# Sheet1.net
KiCad netlist of a schematic drawn in Altium Designer
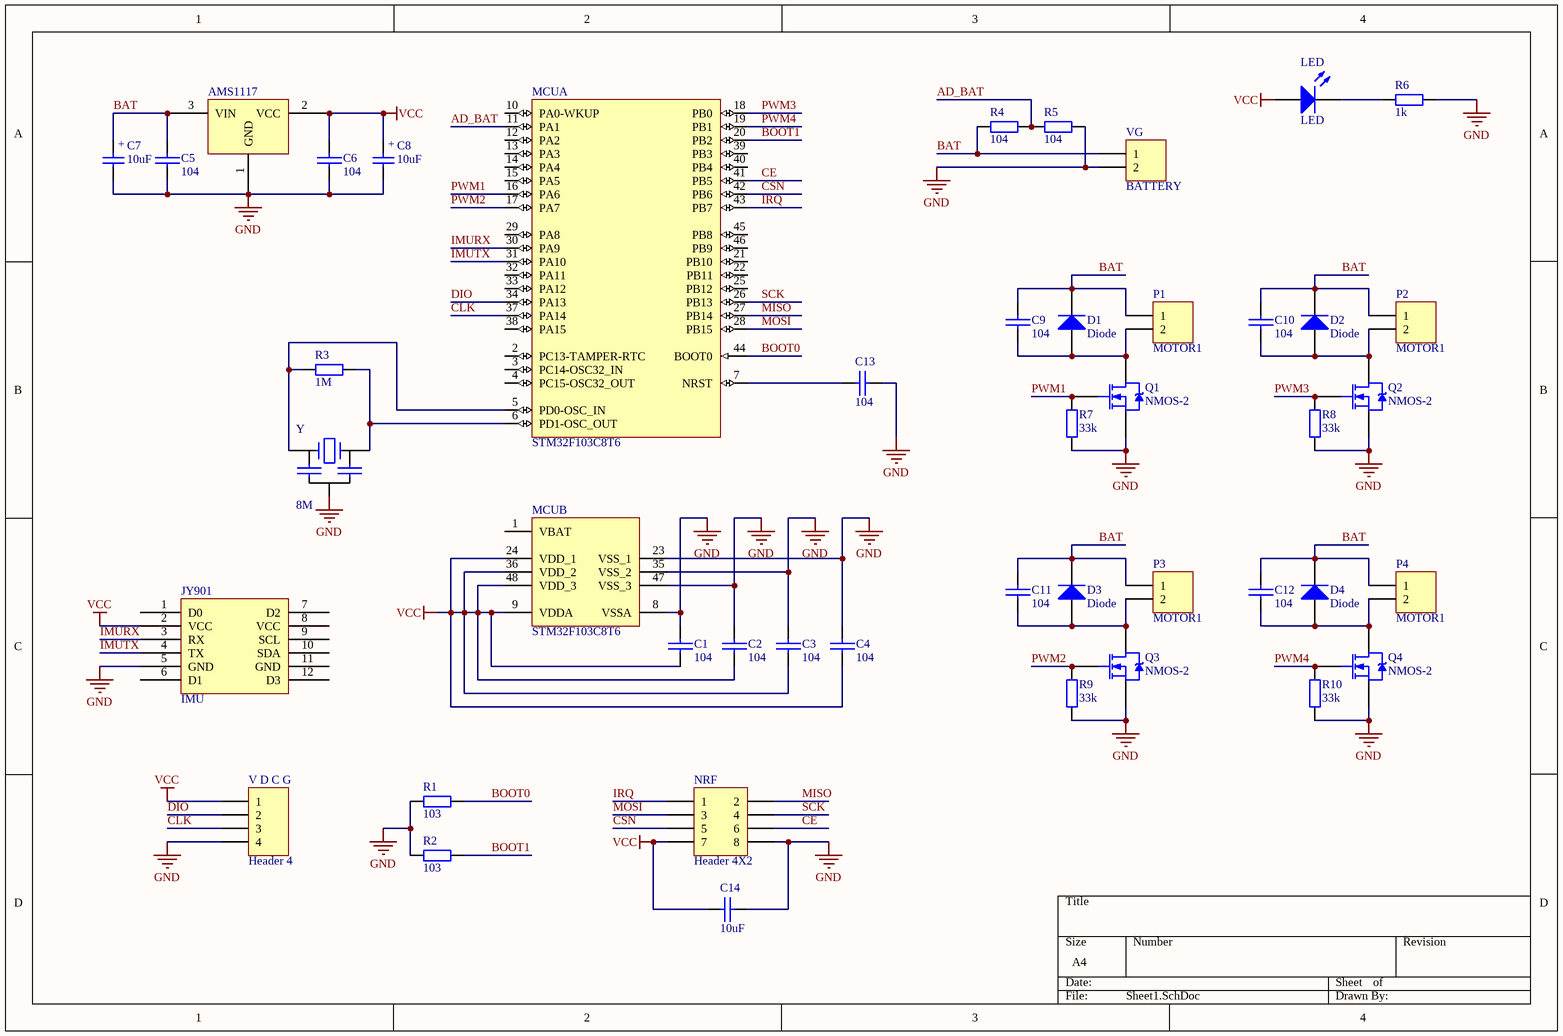
[diagram p0: Sheet1.SchDoc]

(export (version "E")
  (design (tool "Eeschema 10.0.6"))
  (components
    (comp (ref "AMS1117")
      (value "~")
      (footprint "LC-SOT-223")
      (libsource (lib "LC-Standard-FootPrints-AD-V1.00") (part "LC-SOT-233"))
    )
    (comp (ref "C1")
      (value "104")
      (footprint "C1608[0603]N")
      (description "贴片无极性电容")
      (fields (field (name "Comment") "CAP"))
      (libsource (lib "SkyWorks2") (part "CAP"))
    )
    (comp (ref "C2")
      (value "104")
      (footprint "C1608[0603]N")
      (description "贴片无极性电容")
      (fields (field (name "Comment") "CAP"))
      (libsource (lib "SkyWorks2") (part "CAP"))
    )
    (comp (ref "C3")
      (value "104")
      (footprint "C1608[0603]N")
      (description "贴片无极性电容")
      (fields (field (name "Comment") "CAP"))
      (libsource (lib "SkyWorks2") (part "CAP"))
    )
    (comp (ref "C4")
      (value "104")
      (footprint "C1608[0603]N")
      (description "贴片无极性电容")
      (fields (field (name "Comment") "CAP"))
      (libsource (lib "SkyWorks2") (part "CAP"))
    )
    (comp (ref "C5")
      (value "104")
      (footprint "C1608[0603]N")
      (description "贴片无极性电容")
      (fields (field (name "Comment") "cap smd"))
      (libsource (lib "SkyWorks2") (part "CAP"))
    )
    (comp (ref "C6")
      (value "104")
      (footprint "C1608[0603]N")
      (description "贴片无极性电容")
      (fields (field (name "Comment") "cap smd"))
      (libsource (lib "SkyWorks2") (part "CAP"))
    )
    (comp (ref "C7")
      (value "10uF")
      (footprint "C1206")
      (description "贴片极性电容")
      (fields (field (name "Comment") "Cap"))
      (libsource (lib "SkyWorks2") (part "Cap Pol S"))
    )
    (comp (ref "C8")
      (value "10uF")
      (footprint "C1206")
      (description "贴片极性电容")
      (fields (field (name "Comment") "Cap"))
      (libsource (lib "SkyWorks2") (part "Cap Pol S"))
    )
    (comp (ref "C9")
      (value "104")
      (footprint "C1608[0603]N")
      (description "贴片无极性电容")
      (fields (field (name "Comment") "cap smd"))
      (libsource (lib "SkyWorks2") (part "CAP"))
    )
    (comp (ref "C10")
      (value "104")
      (footprint "C1608[0603]N")
      (description "贴片无极性电容")
      (fields (field (name "Comment") "cap smd"))
      (libsource (lib "SkyWorks2") (part "CAP"))
    )
    (comp (ref "C11")
      (value "104")
      (footprint "C1608[0603]N")
      (description "贴片无极性电容")
      (fields (field (name "Comment") "cap smd"))
      (libsource (lib "SkyWorks2") (part "CAP"))
    )
    (comp (ref "C12")
      (value "104")
      (footprint "C1608[0603]N")
      (description "贴片无极性电容")
      (fields (field (name "Comment") "cap smd"))
      (libsource (lib "SkyWorks2") (part "CAP"))
    )
    (comp (ref "C13")
      (value "104")
      (footprint "C1608[0603]N")
      (description "贴片无极性电容")
      (fields (field (name "Comment") "cap smd"))
      (libsource (lib "SkyWorks2") (part "CAP"))
    )
    (comp (ref "C14")
      (value "10uF")
      (footprint "C2012[0805]N")
      (description "贴片无极性电容")
      (fields (field (name "Comment") "cap smd"))
      (libsource (lib "SkyWorks2") (part "CAP"))
    )
    (comp (ref "D1")
      (value "Diode")
      (footprint "D3216[1206]")
      (description "Default Diode")
      (fields (field (name "PUBLISHER") "Altium Limited"))
      (libsource (lib "SkyWorks2") (part "Diode"))
    )
    (comp (ref "D2")
      (value "Diode")
      (footprint "D3216[1206]")
      (description "Default Diode")
      (fields (field (name "PUBLISHER") "Altium Limited"))
      (libsource (lib "SkyWorks2") (part "Diode"))
    )
    (comp (ref "D3")
      (value "Diode")
      (footprint "D3216[1206]")
      (description "Default Diode")
      (fields (field (name "PUBLISHER") "Altium Limited"))
      (libsource (lib "SkyWorks2") (part "Diode"))
    )
    (comp (ref "D4")
      (value "Diode")
      (footprint "D3216[1206]")
      (description "Default Diode")
      (fields (field (name "PUBLISHER") "Altium Limited"))
      (libsource (lib "SkyWorks2") (part "Diode"))
    )
    (comp (ref "JY901") (value "IMU") (footprint "JY-901") (libsource (lib "JYMoudule") (part "JY901")))
    (comp (ref "LED")
      (value "LED")
      (footprint "3.2X1.6X1.1")
      (description "Typical RED, GREEN, YELLOW, AMBER GaAs LED")
      (fields (field (name "PUBLISHER") "Altium Limited"))
      (libsource (lib "SkyWorks2") (part "LED2"))
    )
    (comp (ref "MCU")
      (value "STM32F103C8T6")
      (footprint "STM-LQFP48_N")
      (libsource (lib "STMicroelectronics STM32 F1") (part "STM32F103C8T6"))
    )
    (comp (ref "NRF")
      (value "Header 4X2")
      (footprint "HDR2X4")
      (description "Header, 4-Pin, Dual row")
      (fields (field (name "PUBLISHER") "Altium Limited"))
      (libsource (lib "Miscellaneous Connectors") (part "Header 4X2"))
    )
    (comp (ref "P1")
      (value "MOTOR1")
      (footprint "HDR1X2")
      (description "Header, 2-Pin")
      (fields (field (name "PUBLISHER") "Altium Limited"))
      (libsource (lib "Miscellaneous Connectors") (part "Header 2"))
    )
    (comp (ref "P2")
      (value "MOTOR1")
      (footprint "HDR1X2")
      (description "Header, 2-Pin")
      (fields (field (name "PUBLISHER") "Altium Limited"))
      (libsource (lib "Miscellaneous Connectors") (part "Header 2"))
    )
    (comp (ref "P3")
      (value "MOTOR1")
      (footprint "HDR1X2")
      (description "Header, 2-Pin")
      (fields (field (name "PUBLISHER") "Altium Limited"))
      (libsource (lib "Miscellaneous Connectors") (part "Header 2"))
    )
    (comp (ref "P4")
      (value "MOTOR1")
      (footprint "HDR1X2")
      (description "Header, 2-Pin")
      (fields (field (name "PUBLISHER") "Altium Limited"))
      (libsource (lib "Miscellaneous Connectors") (part "Header 2"))
    )
    (comp (ref "Q1")
      (value "NMOS-2")
      (footprint "LC-SOT-23")
      (description "N-Channel Power MOSFET")
      (fields (field (name "PUBLISHER") "Altium Limited"))
      (libsource (lib "Miscellaneous Devices") (part "NMOS-2"))
    )
    (comp (ref "Q2")
      (value "NMOS-2")
      (footprint "LC-SOT-23")
      (description "N-Channel Power MOSFET")
      (fields (field (name "PUBLISHER") "Altium Limited"))
      (libsource (lib "Miscellaneous Devices") (part "NMOS-2"))
    )
    (comp (ref "Q3")
      (value "NMOS-2")
      (footprint "LC-SOT-23")
      (description "N-Channel Power MOSFET")
      (fields (field (name "PUBLISHER") "Altium Limited"))
      (libsource (lib "Miscellaneous Devices") (part "NMOS-2"))
    )
    (comp (ref "Q4")
      (value "NMOS-2")
      (footprint "LC-SOT-23")
      (description "N-Channel Power MOSFET")
      (fields (field (name "PUBLISHER") "Altium Limited"))
      (libsource (lib "Miscellaneous Devices") (part "NMOS-2"))
    )
    (comp (ref "R1")
      (value "103")
      (footprint "R1608[0603]")
      (fields (field (name "Comment") "RES1"))
      (libsource (lib "SkyWorks2") (part "RES1"))
    )
    (comp (ref "R2")
      (value "103")
      (footprint "R1608[0603]")
      (fields (field (name "Comment") "RES1"))
      (libsource (lib "SkyWorks2") (part "RES1"))
    )
    (comp (ref "R3")
      (value "1M")
      (footprint "R1608[0603]")
      (fields (field (name "Comment") "RES1"))
      (libsource (lib "SkyWorks2") (part "RES1"))
    )
    (comp (ref "R4")
      (value "104")
      (footprint "R1608[0603]")
      (fields (field (name "Comment") "RES1"))
      (libsource (lib "SkyWorks2") (part "RES1"))
    )
    (comp (ref "R5")
      (value "104")
      (footprint "R1608[0603]")
      (fields (field (name "Comment") "RES1"))
      (libsource (lib "SkyWorks2") (part "RES1"))
    )
    (comp (ref "R6")
      (value "1k")
      (footprint "R1608[0603]")
      (fields (field (name "Comment") "RES1"))
      (libsource (lib "SkyWorks2") (part "RES1"))
    )
    (comp (ref "R7")
      (value "33k")
      (footprint "R1608[0603]")
      (fields (field (name "Comment") "RES1"))
      (libsource (lib "SkyWorks2") (part "RES1"))
    )
    (comp (ref "R8")
      (value "33k")
      (footprint "R1608[0603]")
      (fields (field (name "Comment") "RES1"))
      (libsource (lib "SkyWorks2") (part "RES1"))
    )
    (comp (ref "R9")
      (value "33k")
      (footprint "R1608[0603]")
      (fields (field (name "Comment") "RES1"))
      (libsource (lib "SkyWorks2") (part "RES1"))
    )
    (comp (ref "R10")
      (value "33k")
      (footprint "R1608[0603]")
      (fields (field (name "Comment") "RES1"))
      (libsource (lib "SkyWorks2") (part "RES1"))
    )
    (comp (ref "V D C G")
      (value "Header 4")
      (footprint "HDR1X4")
      (description "Header, 4-Pin")
      (fields (field (name "PUBLISHER") "Altium Limited"))
      (libsource (lib "SkyWorks2") (part "Header 4"))
    )
    (comp (ref "VG")
      (value "BATTERY")
      (footprint "HDR1X2")
      (description "Header, 2-Pin")
      (fields (field (name "PUBLISHER") "Altium Limited"))
      (libsource (lib "Miscellaneous Connectors") (part "Header 2"))
    )
    (comp (ref "Y")
      (value "8M")
      (footprint "Crystal_C")
      (description "Crystal")
      (libsource (lib "SkyWorks2") (part "CRYSTAL_C"))
    )
  )
  (nets
    (net (code "1") (name "/AD_BAT") (class "Default")
      (node (ref "MCU") (pin "11") (pinfunction "PA1_11") (pintype "bidirectional"))
      (node (ref "R4") (pin "2") (pinfunction "2_2") (pintype "passive"))
      (node (ref "R5") (pin "1") (pinfunction "1_1") (pintype "passive"))
    )
    (net (code "2") (name "/BAT") (class "Default")
      (node (ref "AMS1117") (pin "3") (pinfunction "VIN_3") (pintype "passive"))
      (node (ref "C10") (pin "1") (pinfunction "1_1") (pintype "passive"))
      (node (ref "C11") (pin "1") (pinfunction "1_1") (pintype "passive"))
      (node (ref "C12") (pin "1") (pinfunction "1_1") (pintype "passive"))
      (node (ref "C5") (pin "1") (pinfunction "1_1") (pintype "passive"))
      (node (ref "C7") (pin "1") (pinfunction "+_1") (pintype "passive"))
      (node (ref "C9") (pin "1") (pinfunction "1_1") (pintype "passive"))
      (node (ref "D1") (pin "2") (pinfunction "K_2") (pintype "passive"))
      (node (ref "D2") (pin "2") (pinfunction "K_2") (pintype "passive"))
      (node (ref "D3") (pin "2") (pinfunction "K_2") (pintype "passive"))
      (node (ref "D4") (pin "2") (pinfunction "K_2") (pintype "passive"))
      (node (ref "P1") (pin "1") (pinfunction "1_1") (pintype "passive"))
      (node (ref "P2") (pin "1") (pinfunction "1_1") (pintype "passive"))
      (node (ref "P3") (pin "1") (pinfunction "1_1") (pintype "passive"))
      (node (ref "P4") (pin "1") (pinfunction "1_1") (pintype "passive"))
      (node (ref "R4") (pin "1") (pinfunction "1_1") (pintype "passive"))
      (node (ref "VG") (pin "1") (pinfunction "1_1") (pintype "passive"))
    )
    (net (code "3") (name "/BOOT0") (class "Default")
      (node (ref "MCU") (pin "44") (pinfunction "BOOT0_44") (pintype "input"))
      (node (ref "R1") (pin "2") (pinfunction "2_2") (pintype "passive"))
    )
    (net (code "4") (name "/BOOT1") (class "Default")
      (node (ref "MCU") (pin "20") (pinfunction "PB2_20") (pintype "bidirectional"))
      (node (ref "R2") (pin "2") (pinfunction "2_2") (pintype "passive"))
    )
    (net (code "5") (name "/CE") (class "Default")
      (node (ref "MCU") (pin "41") (pinfunction "PB5_41") (pintype "bidirectional"))
      (node (ref "NRF") (pin "6") (pinfunction "6_6") (pintype "passive"))
    )
    (net (code "6") (name "/CLK") (class "Default")
      (node (ref "MCU") (pin "37") (pinfunction "PA14_37") (pintype "bidirectional"))
      (node (ref "V D C G") (pin "3") (pinfunction "3_3") (pintype "passive"))
    )
    (net (code "7") (name "/CSN") (class "Default")
      (node (ref "MCU") (pin "42") (pinfunction "PB6_42") (pintype "bidirectional"))
      (node (ref "NRF") (pin "5") (pinfunction "5_5") (pintype "passive"))
    )
    (net (code "8") (name "/DIO") (class "Default")
      (node (ref "MCU") (pin "34") (pinfunction "PA13_34") (pintype "bidirectional"))
      (node (ref "V D C G") (pin "2") (pinfunction "2_2") (pintype "passive"))
    )
    (net (code "9") (name "/IMURX") (class "Default")
      (node (ref "JY901") (pin "3") (pinfunction "RX_3") (pintype "passive"))
      (node (ref "MCU") (pin "30") (pinfunction "PA9_30") (pintype "bidirectional"))
    )
    (net (code "10") (name "/IMUTX") (class "Default")
      (node (ref "JY901") (pin "4") (pinfunction "TX_4") (pintype "passive"))
      (node (ref "MCU") (pin "31") (pinfunction "PA10_31") (pintype "bidirectional"))
    )
    (net (code "11") (name "/IRQ") (class "Default")
      (node (ref "MCU") (pin "43") (pinfunction "PB7_43") (pintype "bidirectional"))
      (node (ref "NRF") (pin "1") (pinfunction "1_1") (pintype "passive"))
    )
    (net (code "12") (name "/MISO") (class "Default")
      (node (ref "MCU") (pin "27") (pinfunction "PB14_27") (pintype "bidirectional"))
      (node (ref "NRF") (pin "2") (pinfunction "2_2") (pintype "passive"))
    )
    (net (code "13") (name "/MOSI") (class "Default")
      (node (ref "MCU") (pin "28") (pinfunction "PB15_28") (pintype "bidirectional"))
      (node (ref "NRF") (pin "3") (pinfunction "3_3") (pintype "passive"))
    )
    (net (code "14") (name "/PWM1") (class "Default")
      (node (ref "MCU") (pin "16") (pinfunction "PA6_16") (pintype "bidirectional"))
      (node (ref "Q1") (pin "1") (pinfunction "G_1") (pintype "passive"))
      (node (ref "R7") (pin "2") (pinfunction "2_2") (pintype "passive"))
    )
    (net (code "15") (name "/PWM2") (class "Default")
      (node (ref "MCU") (pin "17") (pinfunction "PA7_17") (pintype "bidirectional"))
      (node (ref "Q3") (pin "1") (pinfunction "G_1") (pintype "passive"))
      (node (ref "R9") (pin "2") (pinfunction "2_2") (pintype "passive"))
    )
    (net (code "16") (name "/PWM3") (class "Default")
      (node (ref "MCU") (pin "18") (pinfunction "PB0_18") (pintype "bidirectional"))
      (node (ref "Q2") (pin "1") (pinfunction "G_1") (pintype "passive"))
      (node (ref "R8") (pin "2") (pinfunction "2_2") (pintype "passive"))
    )
    (net (code "17") (name "/PWM4") (class "Default")
      (node (ref "MCU") (pin "19") (pinfunction "PB1_19") (pintype "bidirectional"))
      (node (ref "Q4") (pin "1") (pinfunction "G_1") (pintype "passive"))
      (node (ref "R10") (pin "2") (pinfunction "2_2") (pintype "passive"))
    )
    (net (code "18") (name "/SCK") (class "Default")
      (node (ref "MCU") (pin "26") (pinfunction "PB13_26") (pintype "bidirectional"))
      (node (ref "NRF") (pin "4") (pinfunction "4_4") (pintype "passive"))
    )
    (net (code "19") (name "GND") (class "Default")
      (node (ref "AMS1117") (pin "1") (pinfunction "GND_1") (pintype "passive"))
      (node (ref "C1") (pin "1") (pinfunction "1_1") (pintype "passive"))
      (node (ref "C13") (pin "2") (pinfunction "2_2") (pintype "passive"))
      (node (ref "C14") (pin "2") (pinfunction "2_2") (pintype "passive"))
      (node (ref "C2") (pin "1") (pinfunction "1_1") (pintype "passive"))
      (node (ref "C3") (pin "1") (pinfunction "1_1") (pintype "passive"))
      (node (ref "C4") (pin "1") (pinfunction "1_1") (pintype "passive"))
      (node (ref "C5") (pin "2") (pinfunction "2_2") (pintype "passive"))
      (node (ref "C6") (pin "2") (pinfunction "2_2") (pintype "passive"))
      (node (ref "C7") (pin "2") (pinfunction "-_2") (pintype "passive"))
      (node (ref "C8") (pin "2") (pinfunction "-_2") (pintype "passive"))
      (node (ref "JY901") (pin "5") (pinfunction "GND_5") (pintype "passive"))
      (node (ref "MCU") (pin "23") (pinfunction "VSS_1_23") (pintype "power_in"))
      (node (ref "MCU") (pin "35") (pinfunction "VSS_2_35") (pintype "power_in"))
      (node (ref "MCU") (pin "47") (pinfunction "VSS_3_47") (pintype "power_in"))
      (node (ref "MCU") (pin "8") (pinfunction "VSSA_8") (pintype "power_in"))
      (node (ref "NRF") (pin "8") (pinfunction "8_8") (pintype "passive"))
      (node (ref "Q1") (pin "2") (pinfunction "S_2") (pintype "passive"))
      (node (ref "Q2") (pin "2") (pinfunction "S_2") (pintype "passive"))
      (node (ref "Q3") (pin "2") (pinfunction "S_2") (pintype "passive"))
      (node (ref "Q4") (pin "2") (pinfunction "S_2") (pintype "passive"))
      (node (ref "R1") (pin "1") (pinfunction "1_1") (pintype "passive"))
      (node (ref "R10") (pin "1") (pinfunction "1_1") (pintype "passive"))
      (node (ref "R2") (pin "1") (pinfunction "1_1") (pintype "passive"))
      (node (ref "R5") (pin "2") (pinfunction "2_2") (pintype "passive"))
      (node (ref "R6") (pin "2") (pinfunction "2_2") (pintype "passive"))
      (node (ref "R7") (pin "1") (pinfunction "1_1") (pintype "passive"))
      (node (ref "R8") (pin "1") (pinfunction "1_1") (pintype "passive"))
      (node (ref "R9") (pin "1") (pinfunction "1_1") (pintype "passive"))
      (node (ref "V D C G") (pin "4") (pinfunction "4_4") (pintype "passive"))
      (node (ref "VG") (pin "2") (pinfunction "2_2") (pintype "passive"))
      (node (ref "Y") (pin "2") (pinfunction "GND_2") (pintype "passive"))
    )
    (net (code "20") (name "Net-(D1-A)") (class "Default")
      (node (ref "C9") (pin "2") (pinfunction "2_2") (pintype "passive"))
      (node (ref "D1") (pin "1") (pinfunction "A_1") (pintype "passive"))
      (node (ref "P1") (pin "2") (pinfunction "2_2") (pintype "passive"))
      (node (ref "Q1") (pin "3") (pinfunction "D_3") (pintype "passive"))
    )
    (net (code "21") (name "Net-(D2-A)") (class "Default")
      (node (ref "C10") (pin "2") (pinfunction "2_2") (pintype "passive"))
      (node (ref "D2") (pin "1") (pinfunction "A_1") (pintype "passive"))
      (node (ref "P2") (pin "2") (pinfunction "2_2") (pintype "passive"))
      (node (ref "Q2") (pin "3") (pinfunction "D_3") (pintype "passive"))
    )
    (net (code "22") (name "Net-(D3-A)") (class "Default")
      (node (ref "C11") (pin "2") (pinfunction "2_2") (pintype "passive"))
      (node (ref "D3") (pin "1") (pinfunction "A_1") (pintype "passive"))
      (node (ref "P3") (pin "2") (pinfunction "2_2") (pintype "passive"))
      (node (ref "Q3") (pin "3") (pinfunction "D_3") (pintype "passive"))
    )
    (net (code "23") (name "Net-(D4-A)") (class "Default")
      (node (ref "C12") (pin "2") (pinfunction "2_2") (pintype "passive"))
      (node (ref "D4") (pin "1") (pinfunction "A_1") (pintype "passive"))
      (node (ref "P4") (pin "2") (pinfunction "2_2") (pintype "passive"))
      (node (ref "Q4") (pin "3") (pinfunction "D_3") (pintype "passive"))
    )
    (net (code "24") (name "Net-(LED-K)") (class "Default")
      (node (ref "LED") (pin "2") (pinfunction "K_2") (pintype "passive"))
      (node (ref "R6") (pin "1") (pinfunction "1_1") (pintype "passive"))
    )
    (net (code "25") (name "Net-(MCUA-NRST)") (class "Default")
      (node (ref "C13") (pin "1") (pinfunction "1_1") (pintype "passive"))
      (node (ref "MCU") (pin "7") (pinfunction "NRST_7") (pintype "bidirectional"))
    )
    (net (code "26") (name "Net-(MCUA-PD0-OSC_IN)") (class "Default")
      (node (ref "MCU") (pin "5") (pinfunction "PD0-OSC_IN_5") (pintype "bidirectional"))
      (node (ref "R3") (pin "2") (pinfunction "2_2") (pintype "passive"))
      (node (ref "Y") (pin "1") (pinfunction "1_1") (pintype "passive"))
    )
    (net (code "27") (name "Net-(MCUA-PD1-OSC_OUT)") (class "Default")
      (node (ref "MCU") (pin "6") (pinfunction "PD1-OSC_OUT_6") (pintype "bidirectional"))
      (node (ref "R3") (pin "1") (pinfunction "1_1") (pintype "passive"))
      (node (ref "Y") (pin "3") (pinfunction "3_3") (pintype "passive"))
    )
    (net (code "28") (name "VCC") (class "Default")
      (node (ref "AMS1117") (pin "2") (pinfunction "VCC_2") (pintype "passive"))
      (node (ref "C1") (pin "2") (pinfunction "2_2") (pintype "passive"))
      (node (ref "C14") (pin "1") (pinfunction "1_1") (pintype "passive"))
      (node (ref "C2") (pin "2") (pinfunction "2_2") (pintype "passive"))
      (node (ref "C3") (pin "2") (pinfunction "2_2") (pintype "passive"))
      (node (ref "C4") (pin "2") (pinfunction "2_2") (pintype "passive"))
      (node (ref "C6") (pin "1") (pinfunction "1_1") (pintype "passive"))
      (node (ref "C8") (pin "1") (pinfunction "+_1") (pintype "passive"))
      (node (ref "JY901") (pin "2") (pinfunction "VCC_2") (pintype "passive"))
      (node (ref "LED") (pin "1") (pinfunction "A_1") (pintype "passive"))
      (node (ref "MCU") (pin "24") (pinfunction "VDD_1_24") (pintype "power_in"))
      (node (ref "MCU") (pin "36") (pinfunction "VDD_2_36") (pintype "power_in"))
      (node (ref "MCU") (pin "48") (pinfunction "VDD_3_48") (pintype "power_in"))
      (node (ref "MCU") (pin "9") (pinfunction "VDDA_9") (pintype "power_in"))
      (node (ref "NRF") (pin "7") (pinfunction "7_7") (pintype "passive"))
      (node (ref "V D C G") (pin "1") (pinfunction "1_1") (pintype "passive"))
    )
    (net (code "29") (name "unconnected-(JY901-D0-Pad1)") (class "Default")
      (node (ref "JY901") (pin "1") (pinfunction "D0_1") (pintype "passive"))
    )
    (net (code "30") (name "unconnected-(JY901-D1-Pad6)") (class "Default")
      (node (ref "JY901") (pin "6") (pinfunction "D1_6") (pintype "passive"))
    )
    (net (code "31") (name "unconnected-(JY901-D2-Pad7)") (class "Default")
      (node (ref "JY901") (pin "7") (pinfunction "D2_7") (pintype "passive"))
    )
    (net (code "32") (name "unconnected-(JY901-D3-Pad12)") (class "Default")
      (node (ref "JY901") (pin "12") (pinfunction "D3_12") (pintype "passive"))
    )
    (net (code "33") (name "unconnected-(JY901-GND-Pad11)") (class "Default")
      (node (ref "JY901") (pin "11") (pinfunction "GND_11") (pintype "passive"))
    )
    (net (code "34") (name "unconnected-(JY901-SCL-Pad9)") (class "Default")
      (node (ref "JY901") (pin "9") (pinfunction "SCL_9") (pintype "passive"))
    )
    (net (code "35") (name "unconnected-(JY901-SDA-Pad10)") (class "Default")
      (node (ref "JY901") (pin "10") (pinfunction "SDA_10") (pintype "passive"))
    )
    (net (code "36") (name "unconnected-(JY901-VCC-Pad8)") (class "Default")
      (node (ref "JY901") (pin "8") (pinfunction "VCC_8") (pintype "passive"))
    )
    (net (code "37") (name "unconnected-(MCUA-PA0-WKUP-Pad10)") (class "Default")
      (node (ref "MCU") (pin "10") (pinfunction "PA0-WKUP_10") (pintype "bidirectional"))
    )
    (net (code "38") (name "unconnected-(MCUA-PA2-Pad12)") (class "Default")
      (node (ref "MCU") (pin "12") (pinfunction "PA2_12") (pintype "bidirectional"))
    )
    (net (code "39") (name "unconnected-(MCUA-PA3-Pad13)") (class "Default")
      (node (ref "MCU") (pin "13") (pinfunction "PA3_13") (pintype "bidirectional"))
    )
    (net (code "40") (name "unconnected-(MCUA-PA4-Pad14)") (class "Default")
      (node (ref "MCU") (pin "14") (pinfunction "PA4_14") (pintype "bidirectional"))
    )
    (net (code "41") (name "unconnected-(MCUA-PA5-Pad15)") (class "Default")
      (node (ref "MCU") (pin "15") (pinfunction "PA5_15") (pintype "bidirectional"))
    )
    (net (code "42") (name "unconnected-(MCUA-PA8-Pad29)") (class "Default")
      (node (ref "MCU") (pin "29") (pinfunction "PA8_29") (pintype "bidirectional"))
    )
    (net (code "43") (name "unconnected-(MCUA-PA11-Pad32)") (class "Default")
      (node (ref "MCU") (pin "32") (pinfunction "PA11_32") (pintype "bidirectional"))
    )
    (net (code "44") (name "unconnected-(MCUA-PA12-Pad33)") (class "Default")
      (node (ref "MCU") (pin "33") (pinfunction "PA12_33") (pintype "bidirectional"))
    )
    (net (code "45") (name "unconnected-(MCUA-PA15-Pad38)") (class "Default")
      (node (ref "MCU") (pin "38") (pinfunction "PA15_38") (pintype "bidirectional"))
    )
    (net (code "46") (name "unconnected-(MCUA-PB3-Pad39)") (class "Default")
      (node (ref "MCU") (pin "39") (pinfunction "PB3_39") (pintype "bidirectional"))
    )
    (net (code "47") (name "unconnected-(MCUA-PB4-Pad40)") (class "Default")
      (node (ref "MCU") (pin "40") (pinfunction "PB4_40") (pintype "bidirectional"))
    )
    (net (code "48") (name "unconnected-(MCUA-PB8-Pad45)") (class "Default")
      (node (ref "MCU") (pin "45") (pinfunction "PB8_45") (pintype "bidirectional"))
    )
    (net (code "49") (name "unconnected-(MCUA-PB9-Pad46)") (class "Default")
      (node (ref "MCU") (pin "46") (pinfunction "PB9_46") (pintype "bidirectional"))
    )
    (net (code "50") (name "unconnected-(MCUA-PB10-Pad21)") (class "Default")
      (node (ref "MCU") (pin "21") (pinfunction "PB10_21") (pintype "bidirectional"))
    )
    (net (code "51") (name "unconnected-(MCUA-PB11-Pad22)") (class "Default")
      (node (ref "MCU") (pin "22") (pinfunction "PB11_22") (pintype "bidirectional"))
    )
    (net (code "52") (name "unconnected-(MCUA-PB12-Pad25)") (class "Default")
      (node (ref "MCU") (pin "25") (pinfunction "PB12_25") (pintype "bidirectional"))
    )
    (net (code "53") (name "unconnected-(MCUA-PC13-TAMPER-RTC-Pad2)") (class "Default")
      (node (ref "MCU") (pin "2") (pinfunction "PC13-TAMPER-RTC_2") (pintype "bidirectional"))
    )
    (net (code "54") (name "unconnected-(MCUA-PC14-OSC32_IN-Pad3)") (class "Default")
      (node (ref "MCU") (pin "3") (pinfunction "PC14-OSC32_IN_3") (pintype "bidirectional"))
    )
    (net (code "55") (name "unconnected-(MCUA-PC15-OSC32_OUT-Pad4)") (class "Default")
      (node (ref "MCU") (pin "4") (pinfunction "PC15-OSC32_OUT_4") (pintype "bidirectional"))
    )
    (net (code "56") (name "unconnected-(MCUB-VBAT-Pad1)") (class "Default")
      (node (ref "MCU") (pin "1") (pinfunction "VBAT_1") (pintype "power_in"))
    )
  )
)
